# preamp_module_mic_rev2.net
KiCad netlist of a schematic drawn in EAGLE
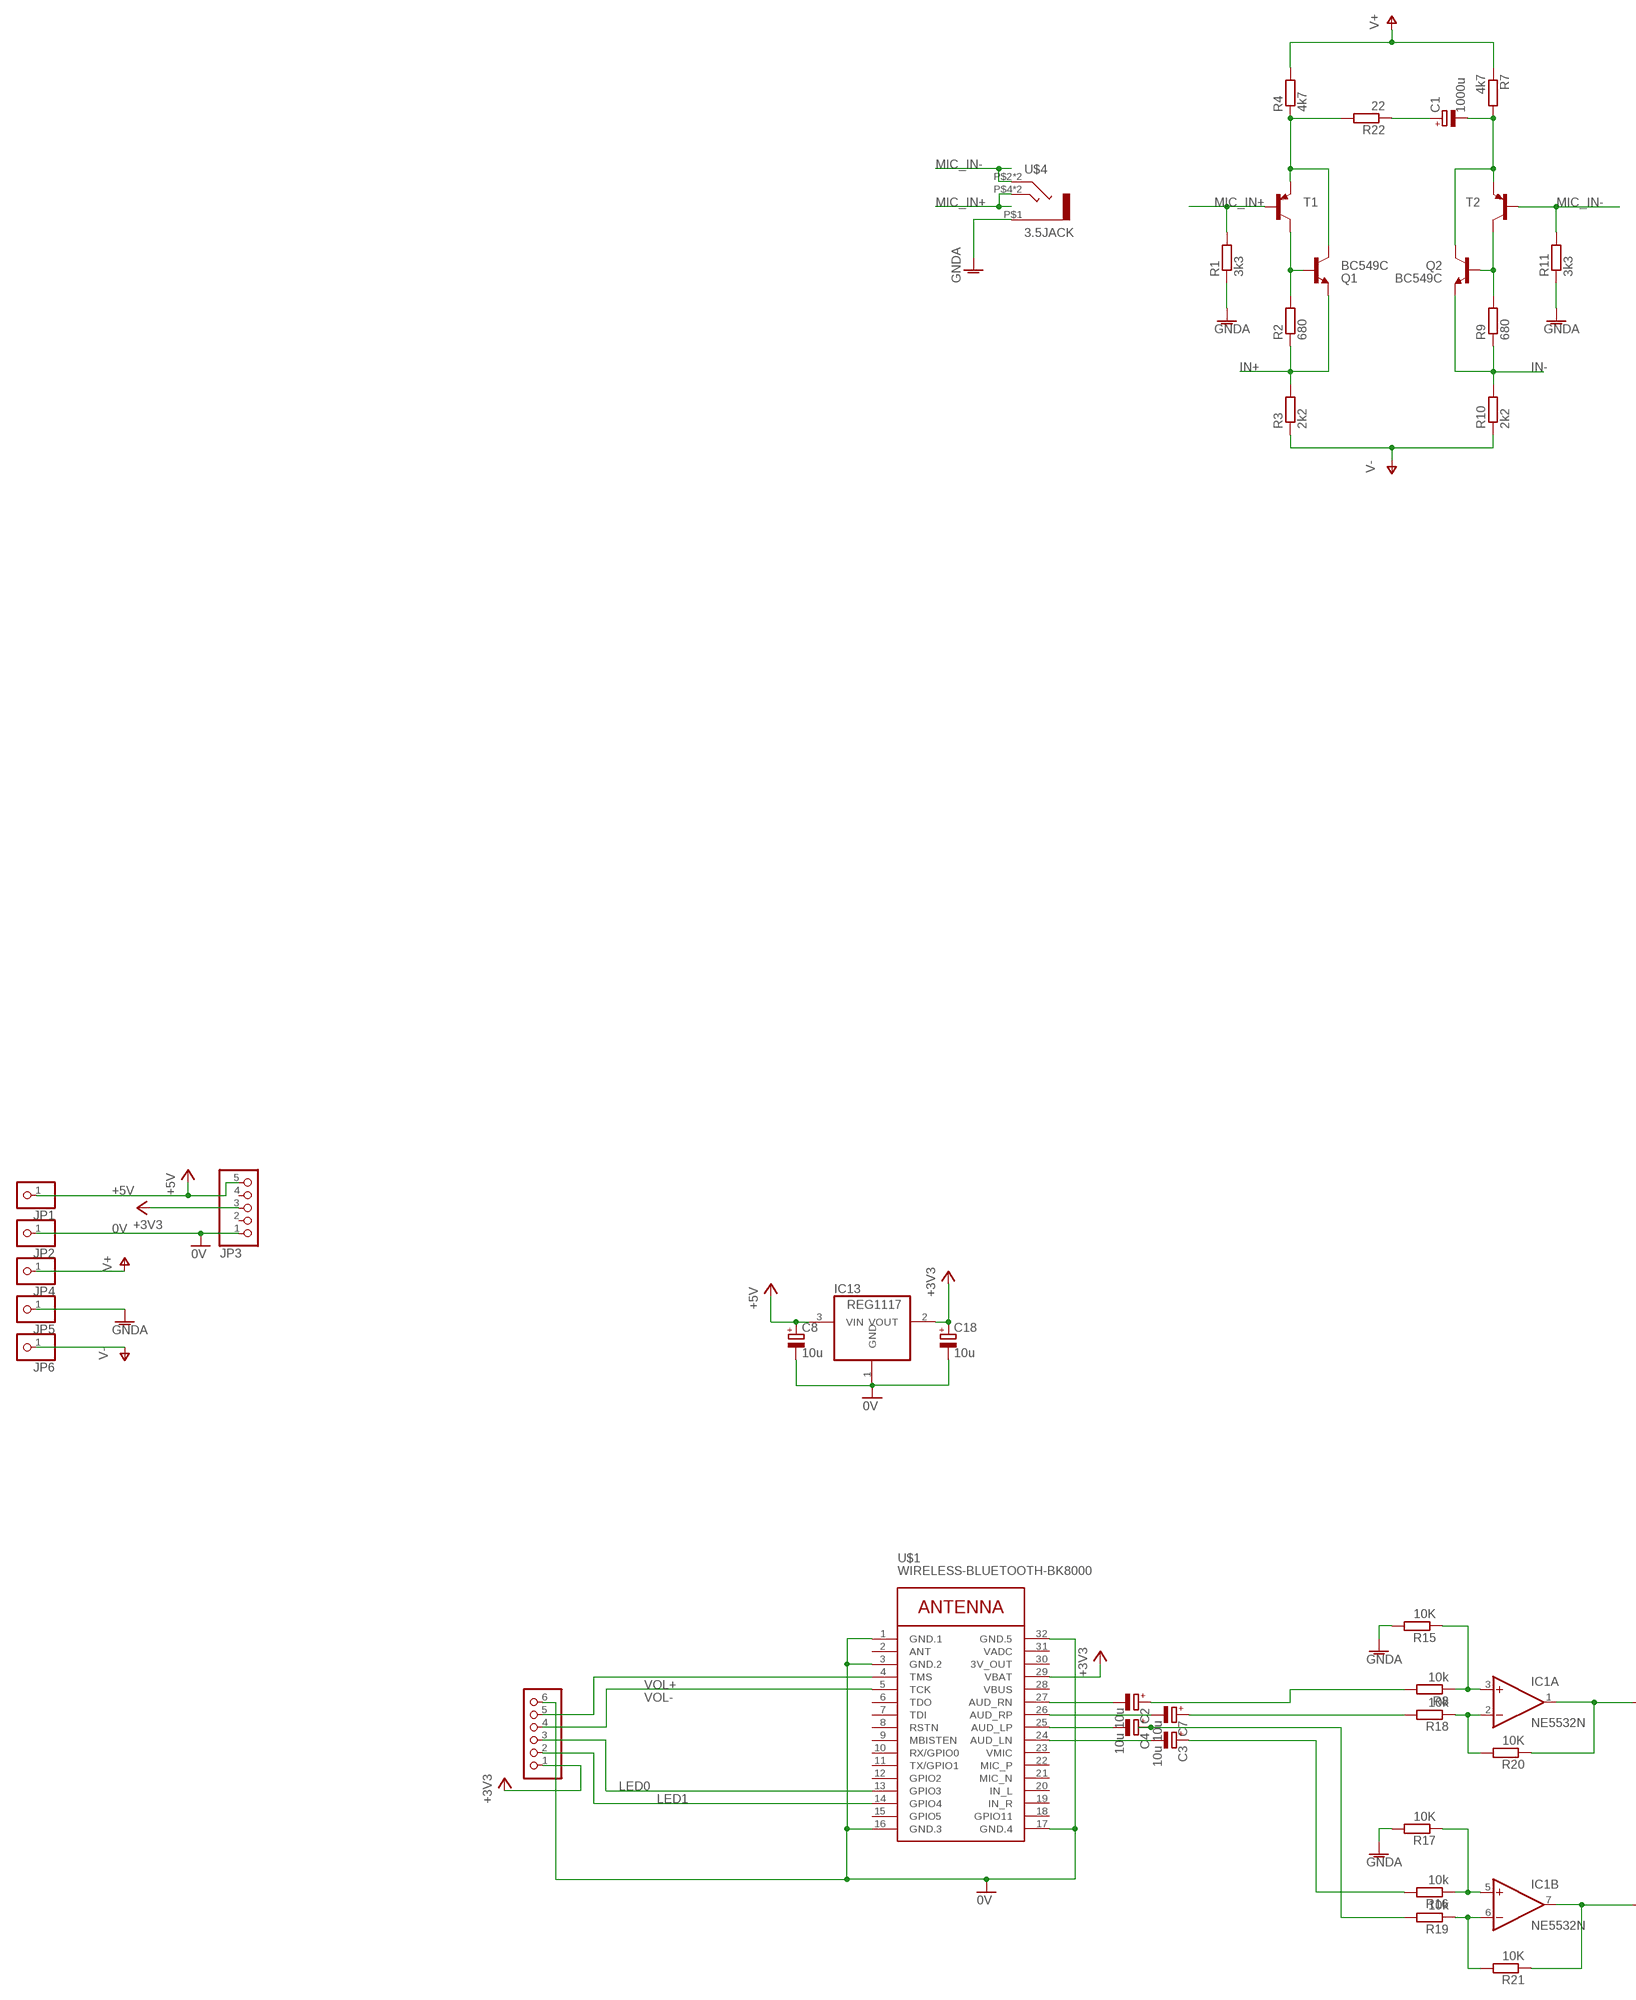
[diagram p0: schematic, sheet 1, part 1 of 2]
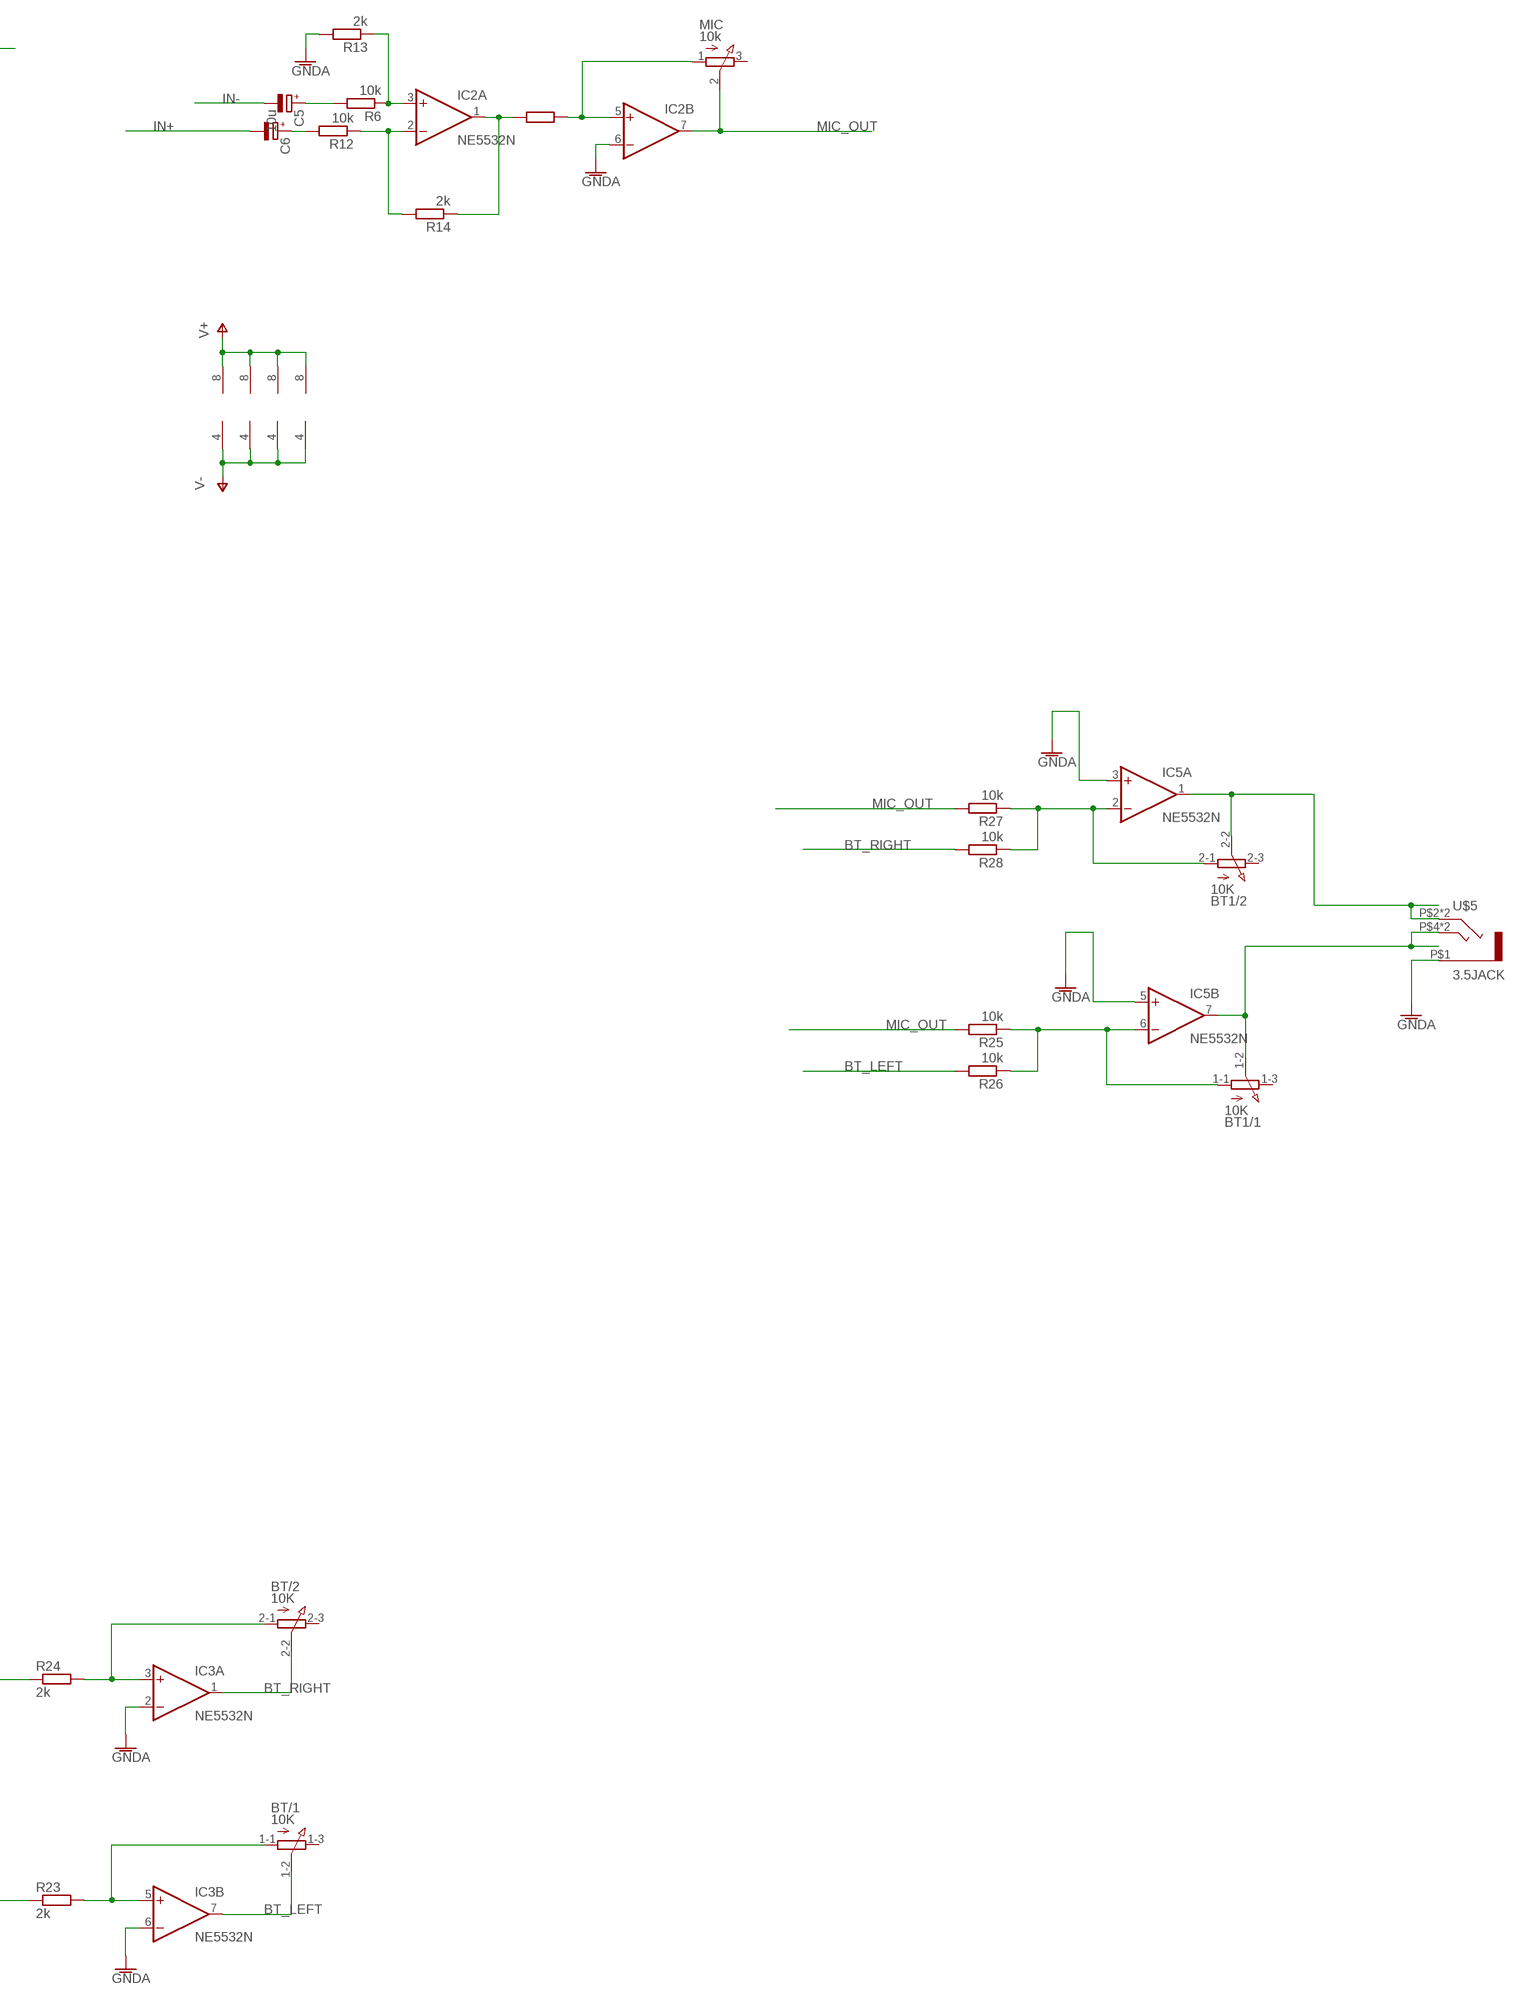
[diagram p1: schematic, sheet 1, part 2 of 2]

(export (version "E")
  (design (tool "Eeschema 10.0.6"))
  (components
    (comp (ref "BT")
      (value "10K")
      (footprint "eagle-import:3RP_1610G")
      (libsource (lib "eagle-import") (part "3RP/1610G"))
    )
    (comp (ref "BT1")
      (value "10K")
      (footprint "eagle-import:3RP_1610G")
      (libsource (lib "eagle-import") (part "3RP/1610G"))
    )
    (comp (ref "C1")
      (value "1000u")
      (footprint "eagle-import:E5-5")
      (libsource (lib "eagle-import") (part "CPOL-EUE5-5"))
    )
    (comp (ref "C2")
      (value "10u")
      (footprint "eagle-import:E2-5")
      (libsource (lib "eagle-import") (part "CPOL-EUE2-5"))
    )
    (comp (ref "C3")
      (value "10u")
      (footprint "eagle-import:E2-5")
      (libsource (lib "eagle-import") (part "CPOL-EUE2-5"))
    )
    (comp (ref "C4")
      (value "10u")
      (footprint "eagle-import:E2-5")
      (libsource (lib "eagle-import") (part "CPOL-EUE2-5"))
    )
    (comp (ref "C5")
      (value "10u")
      (footprint "eagle-import:E2-5")
      (libsource (lib "eagle-import") (part "CPOL-EUE2-5"))
    )
    (comp (ref "C6")
      (value "10u")
      (footprint "eagle-import:E2-5")
      (libsource (lib "eagle-import") (part "CPOL-EUE2-5"))
    )
    (comp (ref "C7")
      (value "10u")
      (footprint "eagle-import:E2-5")
      (libsource (lib "eagle-import") (part "CPOL-EUE2-5"))
    )
    (comp (ref "C8")
      (value "10u")
      (footprint "eagle-import:E2-5")
      (libsource (lib "eagle-import") (part "CPOL-EUE2-5"))
    )
    (comp (ref "C18")
      (value "10u")
      (footprint "eagle-import:E2-5")
      (libsource (lib "eagle-import") (part "CPOL-EUE2-5"))
    )
    (comp (ref "IC1")
      (value "NE5532N")
      (footprint "eagle-import:DIL08")
      (libsource (lib "eagle-import") (part "NE5532N"))
    )
    (comp (ref "IC2")
      (value "NE5532N")
      (footprint "eagle-import:DIL08")
      (libsource (lib "eagle-import") (part "NE5532N"))
    )
    (comp (ref "IC3")
      (value "NE5532N")
      (footprint "eagle-import:DIL08")
      (libsource (lib "eagle-import") (part "NE5532N"))
    )
    (comp (ref "IC5")
      (value "NE5532N")
      (footprint "eagle-import:DIL08")
      (libsource (lib "eagle-import") (part "NE5532N"))
    )
    (comp (ref "IC13")
      (value "REG1117")
      (footprint "eagle-import:SOT223")
      (libsource (lib "eagle-import") (part "REG1117"))
    )
    (comp (ref "JP1")
      (value "PINHD-1X1")
      (footprint "eagle-import:1X01")
      (libsource (lib "eagle-import") (part "PINHD-1X1"))
    )
    (comp (ref "JP2")
      (value "PINHD-1X1")
      (footprint "eagle-import:1X01")
      (libsource (lib "eagle-import") (part "PINHD-1X1"))
    )
    (comp (ref "JP3")
      (value "PINHD-1X5")
      (footprint "eagle-import:1X05")
      (libsource (lib "eagle-import") (part "PINHD-1X5"))
    )
    (comp (ref "JP4")
      (value "PINHD-1X1")
      (footprint "eagle-import:1X01")
      (libsource (lib "eagle-import") (part "PINHD-1X1"))
    )
    (comp (ref "JP5")
      (value "PINHD-1X1")
      (footprint "eagle-import:1X01")
      (libsource (lib "eagle-import") (part "PINHD-1X1"))
    )
    (comp (ref "JP6")
      (value "PINHD-1X1")
      (footprint "eagle-import:1X01")
      (libsource (lib "eagle-import") (part "PINHD-1X1"))
    )
    (comp (ref "JP7")
      (value "PINHD-1X6")
      (footprint "eagle-import:1X06")
      (libsource (lib "eagle-import") (part "PINHD-1X6"))
    )
    (comp (ref "MIC")
      (value "10k")
      (footprint "eagle-import:3RP_1610N")
      (libsource (lib "eagle-import") (part "3RP/1610N"))
    )
    (comp (ref "Q1")
      (value "BC549C")
      (footprint "eagle-import:TO92-EBC")
      (libsource (lib "eagle-import") (part "BC549C"))
    )
    (comp (ref "Q2")
      (value "BC549C")
      (footprint "eagle-import:TO92-EBC")
      (libsource (lib "eagle-import") (part "BC549C"))
    )
    (comp (ref "R1")
      (value "3k3")
      (footprint "eagle-import:0207_10")
      (libsource (lib "eagle-import") (part "R-EU_0207/10"))
    )
    (comp (ref "R2")
      (value "680")
      (footprint "eagle-import:0207_10")
      (libsource (lib "eagle-import") (part "R-EU_0207/10"))
    )
    (comp (ref "R3")
      (value "2k2")
      (footprint "eagle-import:0207_10")
      (libsource (lib "eagle-import") (part "R-EU_0207/10"))
    )
    (comp (ref "R4")
      (value "4k7")
      (footprint "eagle-import:0207_10")
      (libsource (lib "eagle-import") (part "R-EU_0207/10"))
    )
    (comp (ref "R5")
      (value "2k")
      (footprint "eagle-import:0207_10")
      (libsource (lib "eagle-import") (part "R-EU_0207/10"))
    )
    (comp (ref "R6")
      (value "10k")
      (footprint "eagle-import:0207_10")
      (libsource (lib "eagle-import") (part "R-EU_0207/10"))
    )
    (comp (ref "R7")
      (value "4k7")
      (footprint "eagle-import:0207_10")
      (libsource (lib "eagle-import") (part "R-EU_0207/10"))
    )
    (comp (ref "R8")
      (value "10k")
      (footprint "eagle-import:0207_10")
      (libsource (lib "eagle-import") (part "R-EU_0207/10"))
    )
    (comp (ref "R9")
      (value "680")
      (footprint "eagle-import:0207_10")
      (libsource (lib "eagle-import") (part "R-EU_0207/10"))
    )
    (comp (ref "R10")
      (value "2k2")
      (footprint "eagle-import:0207_10")
      (libsource (lib "eagle-import") (part "R-EU_0207/10"))
    )
    (comp (ref "R11")
      (value "3k3")
      (footprint "eagle-import:0207_10")
      (libsource (lib "eagle-import") (part "R-EU_0207/10"))
    )
    (comp (ref "R12")
      (value "10k")
      (footprint "eagle-import:0207_10")
      (libsource (lib "eagle-import") (part "R-EU_0207/10"))
    )
    (comp (ref "R13")
      (value "2k")
      (footprint "eagle-import:0207_10")
      (libsource (lib "eagle-import") (part "R-EU_0207/10"))
    )
    (comp (ref "R14")
      (value "2k")
      (footprint "eagle-import:0207_10")
      (libsource (lib "eagle-import") (part "R-EU_0207/10"))
    )
    (comp (ref "R15")
      (value "10K")
      (footprint "eagle-import:0207_10")
      (libsource (lib "eagle-import") (part "R-EU_0207/10"))
    )
    (comp (ref "R16")
      (value "10k")
      (footprint "eagle-import:0207_10")
      (libsource (lib "eagle-import") (part "R-EU_0207/10"))
    )
    (comp (ref "R17")
      (value "10K")
      (footprint "eagle-import:0207_10")
      (libsource (lib "eagle-import") (part "R-EU_0207/10"))
    )
    (comp (ref "R18")
      (value "10k")
      (footprint "eagle-import:0207_10")
      (libsource (lib "eagle-import") (part "R-EU_0207/10"))
    )
    (comp (ref "R19")
      (value "10k")
      (footprint "eagle-import:0207_10")
      (libsource (lib "eagle-import") (part "R-EU_0207/10"))
    )
    (comp (ref "R20")
      (value "10K")
      (footprint "eagle-import:0207_10")
      (libsource (lib "eagle-import") (part "R-EU_0207/10"))
    )
    (comp (ref "R21")
      (value "10K")
      (footprint "eagle-import:0207_10")
      (libsource (lib "eagle-import") (part "R-EU_0207/10"))
    )
    (comp (ref "R22")
      (value "22")
      (footprint "eagle-import:0207_10")
      (libsource (lib "eagle-import") (part "R-EU_0207/10"))
    )
    (comp (ref "R23")
      (value "2k")
      (footprint "eagle-import:0207_10")
      (libsource (lib "eagle-import") (part "R-EU_0207/10"))
    )
    (comp (ref "R24")
      (value "2k")
      (footprint "eagle-import:0207_10")
      (libsource (lib "eagle-import") (part "R-EU_0207/10"))
    )
    (comp (ref "R25")
      (value "10k")
      (footprint "eagle-import:0207_10")
      (libsource (lib "eagle-import") (part "R-EU_0207/10"))
    )
    (comp (ref "R26")
      (value "10k")
      (footprint "eagle-import:0207_10")
      (libsource (lib "eagle-import") (part "R-EU_0207/10"))
    )
    (comp (ref "R27")
      (value "10k")
      (footprint "eagle-import:0207_10")
      (libsource (lib "eagle-import") (part "R-EU_0207/10"))
    )
    (comp (ref "R28")
      (value "10k")
      (footprint "eagle-import:0207_10")
      (libsource (lib "eagle-import") (part "R-EU_0207/10"))
    )
    (comp (ref "T1")
      (value "2N4403-PNP-TO92-EBC")
      (footprint "eagle-import:TO92-EBC")
      (libsource (lib "eagle-import") (part "-PNP-TO92-EBC2N4403"))
    )
    (comp (ref "T2")
      (value "2N4403-PNP-TO92-EBC")
      (footprint "eagle-import:TO92-EBC")
      (libsource (lib "eagle-import") (part "-PNP-TO92-EBC2N4403"))
    )
    (comp (ref "U$1")
      (value "WIRELESS-BLUETOOTH-BK8000")
      (footprint "eagle-import:WIRELESS-BLUETOOTH-BK8000")
      (libsource (lib "eagle-import") (part "WIRELESS-BLUETOOTH-BK8000"))
    )
    (comp (ref "U$4")
      (value "3.5JACK")
      (footprint "eagle-import:3.5JACK")
      (libsource (lib "eagle-import") (part "3.5JACK"))
    )
    (comp (ref "U$5")
      (value "3.5JACK")
      (footprint "eagle-import:3.5JACK")
      (libsource (lib "eagle-import") (part "3.5JACK"))
    )
  )
  (nets
    (net (code "1") (name "+3V3") (class "Default")
      (node (ref "C18") (pin "+") (pinfunction "+_+") (pintype "passive"))
      (node (ref "IC13") (pin "2") (pinfunction "VOUT_2") (pintype "output"))
      (node (ref "JP3") (pin "3") (pinfunction "3_3") (pintype "passive"))
      (node (ref "JP7") (pin "1") (pinfunction "1_1") (pintype "passive"))
      (node (ref "U$1") (pin "29") (pinfunction "VBAT_29") (pintype "passive"))
    )
    (net (code "2") (name "+5V") (class "Default")
      (node (ref "C8") (pin "+") (pinfunction "+_+") (pintype "passive"))
      (node (ref "IC13") (pin "3") (pinfunction "VIN_3") (pintype "input"))
      (node (ref "JP1") (pin "1") (pinfunction "1_1") (pintype "passive"))
      (node (ref "JP3") (pin "5") (pinfunction "5_5") (pintype "passive"))
    )
    (net (code "3") (name "/3V_OUT") (class "Default")
      (node (ref "U$1") (pin "30") (pinfunction "3V_OUT_30") (pintype "power_in"))
    )
    (net (code "4") (name "/BT_LEFT") (class "Default")
      (node (ref "BT") (pin "1-2") (pinfunction "S_1-2") (pintype "passive"))
      (node (ref "IC3") (pin "7") (pinfunction "OUT_7") (pintype "output"))
      (node (ref "R26") (pin "2") (pinfunction "2_2") (pintype "passive"))
    )
    (net (code "5") (name "/BT_RIGHT") (class "Default")
      (node (ref "BT") (pin "2-2") (pinfunction "S_2-2") (pintype "passive"))
      (node (ref "IC3") (pin "1") (pinfunction "OUT_1") (pintype "output"))
      (node (ref "R28") (pin "2") (pinfunction "2_2") (pintype "passive"))
    )
    (net (code "6") (name "/IN+") (class "Default")
      (node (ref "C6") (pin "-") (pinfunction "-_-") (pintype "passive"))
      (node (ref "Q1") (pin "E") (pinfunction "E_E") (pintype "passive"))
      (node (ref "R2") (pin "1") (pinfunction "1_1") (pintype "passive"))
      (node (ref "R3") (pin "2") (pinfunction "2_2") (pintype "passive"))
    )
    (net (code "7") (name "/IN-") (class "Default")
      (node (ref "C5") (pin "-") (pinfunction "-_-") (pintype "passive"))
      (node (ref "Q2") (pin "E") (pinfunction "E_E") (pintype "passive"))
      (node (ref "R10") (pin "2") (pinfunction "2_2") (pintype "passive"))
      (node (ref "R9") (pin "1") (pinfunction "1_1") (pintype "passive"))
    )
    (net (code "8") (name "/LED0") (class "Default")
      (node (ref "JP7") (pin "3") (pinfunction "3_3") (pintype "passive"))
      (node (ref "U$1") (pin "13") (pinfunction "GPIO3_13") (pintype "bidirectional"))
    )
    (net (code "9") (name "/LED1") (class "Default")
      (node (ref "JP7") (pin "2") (pinfunction "2_2") (pintype "passive"))
      (node (ref "U$1") (pin "14") (pinfunction "GPIO4_14") (pintype "bidirectional"))
    )
    (net (code "10") (name "/MIC_IN+") (class "Default")
      (node (ref "R1") (pin "2") (pinfunction "2_2") (pintype "passive"))
      (node (ref "T1") (pin "B") (pinfunction "B_B") (pintype "passive"))
      (node (ref "U$4") (pin "P$4") (pinfunction "3_P$4") (pintype "passive"))
      (node (ref "U$4") (pin "P$5") (pinfunction "3_P$5") (pintype "passive"))
    )
    (net (code "11") (name "/MIC_IN-") (class "Default")
      (node (ref "R11") (pin "2") (pinfunction "2_2") (pintype "passive"))
      (node (ref "T2") (pin "B") (pinfunction "B_B") (pintype "passive"))
      (node (ref "U$4") (pin "P$2") (pinfunction "2_P$2") (pintype "passive"))
      (node (ref "U$4") (pin "P$3") (pinfunction "2_P$3") (pintype "passive"))
    )
    (net (code "12") (name "/MIC_OUT") (class "Default")
      (node (ref "IC2") (pin "7") (pinfunction "OUT_7") (pintype "output"))
      (node (ref "MIC") (pin "2") (pinfunction "S_2") (pintype "passive"))
      (node (ref "R25") (pin "2") (pinfunction "2_2") (pintype "passive"))
      (node (ref "R27") (pin "2") (pinfunction "2_2") (pintype "passive"))
    )
    (net (code "13") (name "/VADC") (class "Default")
      (node (ref "U$1") (pin "31") (pinfunction "VADC_31") (pintype "power_in"))
    )
    (net (code "14") (name "/VOL+") (class "Default")
      (node (ref "JP7") (pin "5") (pinfunction "5_5") (pintype "passive"))
      (node (ref "U$1") (pin "4") (pinfunction "TMS_4") (pintype "bidirectional"))
    )
    (net (code "15") (name "/VOL-") (class "Default")
      (node (ref "JP7") (pin "4") (pinfunction "4_4") (pintype "passive"))
      (node (ref "U$1") (pin "5") (pinfunction "TCK_5") (pintype "bidirectional"))
    )
    (net (code "16") (name "0V") (class "Default")
      (node (ref "C18") (pin "-") (pinfunction "-_-") (pintype "passive"))
      (node (ref "C8") (pin "-") (pinfunction "-_-") (pintype "passive"))
      (node (ref "IC13") (pin "1") (pinfunction "GND_1") (pintype "power_in"))
      (node (ref "JP2") (pin "1") (pinfunction "1_1") (pintype "passive"))
      (node (ref "JP3") (pin "1") (pinfunction "1_1") (pintype "passive"))
      (node (ref "JP7") (pin "6") (pinfunction "6_6") (pintype "passive"))
      (node (ref "U$1") (pin "1") (pinfunction "GND.1_1") (pintype "power_in"))
      (node (ref "U$1") (pin "16") (pinfunction "GND.3_16") (pintype "power_in"))
      (node (ref "U$1") (pin "17") (pinfunction "GND.4_17") (pintype "power_in"))
      (node (ref "U$1") (pin "3") (pinfunction "GND.2_3") (pintype "power_in"))
      (node (ref "U$1") (pin "32") (pinfunction "GND.5_32") (pintype "power_in"))
    )
    (net (code "17") (name "GNDA") (class "Default")
      (node (ref "IC2") (pin "6") (pinfunction "-IN_6") (pintype "input"))
      (node (ref "IC3") (pin "2") (pinfunction "-IN_2") (pintype "input"))
      (node (ref "IC3") (pin "6") (pinfunction "-IN_6") (pintype "input"))
      (node (ref "IC5") (pin "3") (pinfunction "+IN_3") (pintype "input"))
      (node (ref "IC5") (pin "5") (pinfunction "+IN_5") (pintype "input"))
      (node (ref "JP5") (pin "1") (pinfunction "1_1") (pintype "passive"))
      (node (ref "R1") (pin "1") (pinfunction "1_1") (pintype "passive"))
      (node (ref "R11") (pin "1") (pinfunction "1_1") (pintype "passive"))
      (node (ref "R13") (pin "2") (pinfunction "2_2") (pintype "passive"))
      (node (ref "R15") (pin "2") (pinfunction "2_2") (pintype "passive"))
      (node (ref "R17") (pin "2") (pinfunction "2_2") (pintype "passive"))
      (node (ref "U$4") (pin "P$1") (pinfunction "1_P$1") (pintype "passive"))
      (node (ref "U$5") (pin "P$1") (pinfunction "1_P$1") (pintype "passive"))
    )
    (net (code "18") (name "Net-(BT1A-A)") (class "Default")
      (node (ref "BT1") (pin "1-1") (pinfunction "A_1-1") (pintype "passive"))
      (node (ref "IC5") (pin "6") (pinfunction "-IN_6") (pintype "input"))
      (node (ref "R25") (pin "1") (pinfunction "1_1") (pintype "passive"))
      (node (ref "R26") (pin "1") (pinfunction "1_1") (pintype "passive"))
    )
    (net (code "19") (name "Net-(BT1A-S)") (class "Default")
      (node (ref "BT1") (pin "1-2") (pinfunction "S_1-2") (pintype "passive"))
      (node (ref "IC5") (pin "7") (pinfunction "OUT_7") (pintype "output"))
      (node (ref "U$5") (pin "P$4") (pinfunction "3_P$4") (pintype "passive"))
      (node (ref "U$5") (pin "P$5") (pinfunction "3_P$5") (pintype "passive"))
    )
    (net (code "20") (name "Net-(BT1B-A)") (class "Default")
      (node (ref "BT1") (pin "2-1") (pinfunction "A_2-1") (pintype "passive"))
      (node (ref "IC5") (pin "2") (pinfunction "-IN_2") (pintype "input"))
      (node (ref "R27") (pin "1") (pinfunction "1_1") (pintype "passive"))
      (node (ref "R28") (pin "1") (pinfunction "1_1") (pintype "passive"))
    )
    (net (code "21") (name "Net-(BT1B-S)") (class "Default")
      (node (ref "BT1") (pin "2-2") (pinfunction "S_2-2") (pintype "passive"))
      (node (ref "IC5") (pin "1") (pinfunction "OUT_1") (pintype "output"))
      (node (ref "U$5") (pin "P$2") (pinfunction "2_P$2") (pintype "passive"))
      (node (ref "U$5") (pin "P$3") (pinfunction "2_P$3") (pintype "passive"))
    )
    (net (code "22") (name "Net-(BTA-A)") (class "Default")
      (node (ref "BT") (pin "1-1") (pinfunction "A_1-1") (pintype "passive"))
      (node (ref "IC3") (pin "5") (pinfunction "+IN_5") (pintype "input"))
      (node (ref "R23") (pin "2") (pinfunction "2_2") (pintype "passive"))
    )
    (net (code "23") (name "Net-(BTB-A)") (class "Default")
      (node (ref "BT") (pin "2-1") (pinfunction "A_2-1") (pintype "passive"))
      (node (ref "IC3") (pin "3") (pinfunction "+IN_3") (pintype "input"))
      (node (ref "R24") (pin "2") (pinfunction "2_2") (pintype "passive"))
    )
    (net (code "24") (name "Net-(C1-Pad+)") (class "Default")
      (node (ref "C1") (pin "+") (pinfunction "+_+") (pintype "passive"))
      (node (ref "R22") (pin "1") (pinfunction "1_1") (pintype "passive"))
    )
    (net (code "25") (name "Net-(C1-Pad-)") (class "Default")
      (node (ref "C1") (pin "-") (pinfunction "-_-") (pintype "passive"))
      (node (ref "Q2") (pin "C") (pinfunction "C_C") (pintype "passive"))
      (node (ref "R7") (pin "2") (pinfunction "2_2") (pintype "passive"))
      (node (ref "T2") (pin "E") (pinfunction "E_E") (pintype "passive"))
    )
    (net (code "26") (name "Net-(C2-Pad+)") (class "Default")
      (node (ref "C2") (pin "+") (pinfunction "+_+") (pintype "passive"))
      (node (ref "R8") (pin "2") (pinfunction "2_2") (pintype "passive"))
    )
    (net (code "27") (name "Net-(C3-Pad+)") (class "Default")
      (node (ref "C3") (pin "+") (pinfunction "+_+") (pintype "passive"))
      (node (ref "R16") (pin "2") (pinfunction "2_2") (pintype "passive"))
    )
    (net (code "28") (name "Net-(C4-Pad+)") (class "Default")
      (node (ref "C4") (pin "+") (pinfunction "+_+") (pintype "passive"))
      (node (ref "R19") (pin "2") (pinfunction "2_2") (pintype "passive"))
    )
    (net (code "29") (name "Net-(C5-Pad+)") (class "Default")
      (node (ref "C5") (pin "+") (pinfunction "+_+") (pintype "passive"))
      (node (ref "R6") (pin "2") (pinfunction "2_2") (pintype "passive"))
    )
    (net (code "30") (name "Net-(C6-Pad+)") (class "Default")
      (node (ref "C6") (pin "+") (pinfunction "+_+") (pintype "passive"))
      (node (ref "R12") (pin "2") (pinfunction "2_2") (pintype "passive"))
    )
    (net (code "31") (name "Net-(C7-Pad+)") (class "Default")
      (node (ref "C7") (pin "+") (pinfunction "+_+") (pintype "passive"))
      (node (ref "R18") (pin "2") (pinfunction "2_2") (pintype "passive"))
    )
    (net (code "32") (name "Net-(IC1A-+IN)") (class "Default")
      (node (ref "IC1") (pin "3") (pinfunction "+IN_3") (pintype "input"))
      (node (ref "R15") (pin "1") (pinfunction "1_1") (pintype "passive"))
      (node (ref "R8") (pin "1") (pinfunction "1_1") (pintype "passive"))
    )
    (net (code "33") (name "Net-(IC1A--IN)") (class "Default")
      (node (ref "IC1") (pin "2") (pinfunction "-IN_2") (pintype "input"))
      (node (ref "R18") (pin "1") (pinfunction "1_1") (pintype "passive"))
      (node (ref "R20") (pin "2") (pinfunction "2_2") (pintype "passive"))
    )
    (net (code "34") (name "Net-(IC1A-OUT)") (class "Default")
      (node (ref "IC1") (pin "1") (pinfunction "OUT_1") (pintype "output"))
      (node (ref "R20") (pin "1") (pinfunction "1_1") (pintype "passive"))
      (node (ref "R24") (pin "1") (pinfunction "1_1") (pintype "passive"))
    )
    (net (code "35") (name "Net-(IC1B-+IN)") (class "Default")
      (node (ref "IC1") (pin "5") (pinfunction "+IN_5") (pintype "input"))
      (node (ref "R16") (pin "1") (pinfunction "1_1") (pintype "passive"))
      (node (ref "R17") (pin "1") (pinfunction "1_1") (pintype "passive"))
    )
    (net (code "36") (name "Net-(IC1B--IN)") (class "Default")
      (node (ref "IC1") (pin "6") (pinfunction "-IN_6") (pintype "input"))
      (node (ref "R19") (pin "1") (pinfunction "1_1") (pintype "passive"))
      (node (ref "R21") (pin "2") (pinfunction "2_2") (pintype "passive"))
    )
    (net (code "37") (name "Net-(IC1B-OUT)") (class "Default")
      (node (ref "IC1") (pin "7") (pinfunction "OUT_7") (pintype "output"))
      (node (ref "R21") (pin "1") (pinfunction "1_1") (pintype "passive"))
      (node (ref "R23") (pin "1") (pinfunction "1_1") (pintype "passive"))
    )
    (net (code "38") (name "Net-(IC2A-+IN)") (class "Default")
      (node (ref "IC2") (pin "3") (pinfunction "+IN_3") (pintype "input"))
      (node (ref "R13") (pin "1") (pinfunction "1_1") (pintype "passive"))
      (node (ref "R6") (pin "1") (pinfunction "1_1") (pintype "passive"))
    )
    (net (code "39") (name "Net-(IC2A--IN)") (class "Default")
      (node (ref "IC2") (pin "2") (pinfunction "-IN_2") (pintype "input"))
      (node (ref "R12") (pin "1") (pinfunction "1_1") (pintype "passive"))
      (node (ref "R14") (pin "2") (pinfunction "2_2") (pintype "passive"))
    )
    (net (code "40") (name "Net-(IC2A-OUT)") (class "Default")
      (node (ref "IC2") (pin "1") (pinfunction "OUT_1") (pintype "output"))
      (node (ref "R14") (pin "1") (pinfunction "1_1") (pintype "passive"))
      (node (ref "R5") (pin "1") (pinfunction "1_1") (pintype "passive"))
    )
    (net (code "41") (name "Net-(IC2B-+IN)") (class "Default")
      (node (ref "IC2") (pin "5") (pinfunction "+IN_5") (pintype "input"))
      (node (ref "MIC") (pin "1") (pinfunction "A_1") (pintype "passive"))
      (node (ref "R5") (pin "2") (pinfunction "2_2") (pintype "passive"))
    )
    (net (code "42") (name "Net-(Q1-PadB)") (class "Default")
      (node (ref "Q1") (pin "B") (pinfunction "B_B") (pintype "passive"))
      (node (ref "R2") (pin "2") (pinfunction "2_2") (pintype "passive"))
      (node (ref "T1") (pin "C") (pinfunction "C_C") (pintype "passive"))
    )
    (net (code "43") (name "Net-(Q1-PadC)") (class "Default")
      (node (ref "Q1") (pin "C") (pinfunction "C_C") (pintype "passive"))
      (node (ref "R22") (pin "2") (pinfunction "2_2") (pintype "passive"))
      (node (ref "R4") (pin "1") (pinfunction "1_1") (pintype "passive"))
      (node (ref "T1") (pin "E") (pinfunction "E_E") (pintype "passive"))
    )
    (net (code "44") (name "Net-(Q2-PadB)") (class "Default")
      (node (ref "Q2") (pin "B") (pinfunction "B_B") (pintype "passive"))
      (node (ref "R9") (pin "2") (pinfunction "2_2") (pintype "passive"))
      (node (ref "T2") (pin "C") (pinfunction "C_C") (pintype "passive"))
    )
    (net (code "45") (name "Net-(U$1-AUD_LN)") (class "Default")
      (node (ref "C3") (pin "-") (pinfunction "-_-") (pintype "passive"))
      (node (ref "U$1") (pin "24") (pinfunction "AUD_LN_24") (pintype "output"))
    )
    (net (code "46") (name "Net-(U$1-AUD_LP)") (class "Default")
      (node (ref "C4") (pin "-") (pinfunction "-_-") (pintype "passive"))
      (node (ref "U$1") (pin "25") (pinfunction "AUD_LP_25") (pintype "output"))
    )
    (net (code "47") (name "Net-(U$1-AUD_RN)") (class "Default")
      (node (ref "C2") (pin "-") (pinfunction "-_-") (pintype "passive"))
      (node (ref "U$1") (pin "27") (pinfunction "AUD_RN_27") (pintype "output"))
    )
    (net (code "48") (name "Net-(U$1-AUD_RP)") (class "Default")
      (node (ref "C7") (pin "-") (pinfunction "-_-") (pintype "passive"))
      (node (ref "U$1") (pin "26") (pinfunction "AUD_RP_26") (pintype "output"))
    )
    (net (code "49") (name "V+") (class "Default")
      (node (ref "IC1") (pin "8") (pinfunction "V+_8") (pintype "power_in"))
      (node (ref "IC2") (pin "8") (pinfunction "V+_8") (pintype "power_in"))
      (node (ref "IC3") (pin "8") (pinfunction "V+_8") (pintype "power_in"))
      (node (ref "IC5") (pin "8") (pinfunction "V+_8") (pintype "power_in"))
      (node (ref "JP4") (pin "1") (pinfunction "1_1") (pintype "passive"))
      (node (ref "R4") (pin "2") (pinfunction "2_2") (pintype "passive"))
      (node (ref "R7") (pin "1") (pinfunction "1_1") (pintype "passive"))
    )
    (net (code "50") (name "V-") (class "Default")
      (node (ref "IC1") (pin "4") (pinfunction "V-_4") (pintype "power_in"))
      (node (ref "IC2") (pin "4") (pinfunction "V-_4") (pintype "power_in"))
      (node (ref "IC3") (pin "4") (pinfunction "V-_4") (pintype "power_in"))
      (node (ref "IC5") (pin "4") (pinfunction "V-_4") (pintype "power_in"))
      (node (ref "JP6") (pin "1") (pinfunction "1_1") (pintype "passive"))
      (node (ref "R10") (pin "1") (pinfunction "1_1") (pintype "passive"))
      (node (ref "R3") (pin "1") (pinfunction "1_1") (pintype "passive"))
    )
    (net (code "51") (name "unconnected-(BT1A-E-Pad1-3)") (class "Default")
      (node (ref "BT1") (pin "1-3") (pinfunction "E_1-3") (pintype "passive"))
    )
    (net (code "52") (name "unconnected-(BT1B-E-Pad2-3)") (class "Default")
      (node (ref "BT1") (pin "2-3") (pinfunction "E_2-3") (pintype "passive"))
    )
    (net (code "53") (name "unconnected-(BTA-E-Pad1-3)") (class "Default")
      (node (ref "BT") (pin "1-3") (pinfunction "E_1-3") (pintype "passive"))
    )
    (net (code "54") (name "unconnected-(BTB-E-Pad2-3)") (class "Default")
      (node (ref "BT") (pin "2-3") (pinfunction "E_2-3") (pintype "passive"))
    )
    (net (code "55") (name "unconnected-(JP3-Pad2)") (class "Default")
      (node (ref "JP3") (pin "2") (pinfunction "2_2") (pintype "passive"))
    )
    (net (code "56") (name "unconnected-(JP3-Pad4)") (class "Default")
      (node (ref "JP3") (pin "4") (pinfunction "4_4") (pintype "passive"))
    )
    (net (code "57") (name "unconnected-(MIC-E-Pad3)") (class "Default")
      (node (ref "MIC") (pin "3") (pinfunction "E_3") (pintype "passive"))
    )
    (net (code "58") (name "unconnected-(U$1-ANT-Pad2)") (class "Default")
      (node (ref "U$1") (pin "2") (pinfunction "ANT_2") (pintype "passive"))
    )
    (net (code "59") (name "unconnected-(U$1-GPIO2-Pad12)") (class "Default")
      (node (ref "U$1") (pin "12") (pinfunction "GPIO2_12") (pintype "bidirectional"))
    )
    (net (code "60") (name "unconnected-(U$1-GPIO5-Pad15)") (class "Default")
      (node (ref "U$1") (pin "15") (pinfunction "GPIO5_15") (pintype "bidirectional"))
    )
    (net (code "61") (name "unconnected-(U$1-GPIO11-Pad18)") (class "Default")
      (node (ref "U$1") (pin "18") (pinfunction "GPIO11_18") (pintype "bidirectional"))
    )
    (net (code "62") (name "unconnected-(U$1-IN_L-Pad20)") (class "Default")
      (node (ref "U$1") (pin "20") (pinfunction "IN_L_20") (pintype "input"))
    )
    (net (code "63") (name "unconnected-(U$1-IN_R-Pad19)") (class "Default")
      (node (ref "U$1") (pin "19") (pinfunction "IN_R_19") (pintype "input"))
    )
    (net (code "64") (name "unconnected-(U$1-MBISTEN-Pad9)") (class "Default")
      (node (ref "U$1") (pin "9") (pinfunction "MBISTEN_9") (pintype "bidirectional"))
    )
    (net (code "65") (name "unconnected-(U$1-MIC_N-Pad21)") (class "Default")
      (node (ref "U$1") (pin "21") (pinfunction "MIC_N_21") (pintype "input"))
    )
    (net (code "66") (name "unconnected-(U$1-MIC_P-Pad22)") (class "Default")
      (node (ref "U$1") (pin "22") (pinfunction "MIC_P_22") (pintype "input"))
    )
    (net (code "67") (name "unconnected-(U$1-RSTN-Pad8)") (class "Default")
      (node (ref "U$1") (pin "8") (pinfunction "RSTN_8") (pintype "bidirectional"))
    )
    (net (code "68") (name "unconnected-(U$1-RX{slash}GPIO0-Pad10)") (class "Default")
      (node (ref "U$1") (pin "10") (pinfunction "RX/GPIO0_10") (pintype "bidirectional"))
    )
    (net (code "69") (name "unconnected-(U$1-TDI-Pad7)") (class "Default")
      (node (ref "U$1") (pin "7") (pinfunction "TDI_7") (pintype "bidirectional"))
    )
    (net (code "70") (name "unconnected-(U$1-TDO-Pad6)") (class "Default")
      (node (ref "U$1") (pin "6") (pinfunction "TDO_6") (pintype "bidirectional"))
    )
    (net (code "71") (name "unconnected-(U$1-TX{slash}GPIO1-Pad11)") (class "Default")
      (node (ref "U$1") (pin "11") (pinfunction "TX/GPIO1_11") (pintype "bidirectional"))
    )
    (net (code "72") (name "unconnected-(U$1-VBUS-Pad28)") (class "Default")
      (node (ref "U$1") (pin "28") (pinfunction "VBUS_28") (pintype "passive"))
    )
    (net (code "73") (name "unconnected-(U$1-VMIC-Pad23)") (class "Default")
      (node (ref "U$1") (pin "23") (pinfunction "VMIC_23") (pintype "passive"))
    )
  )
)
